# main.net
KiCad netlist of a schematic drawn in EAGLE
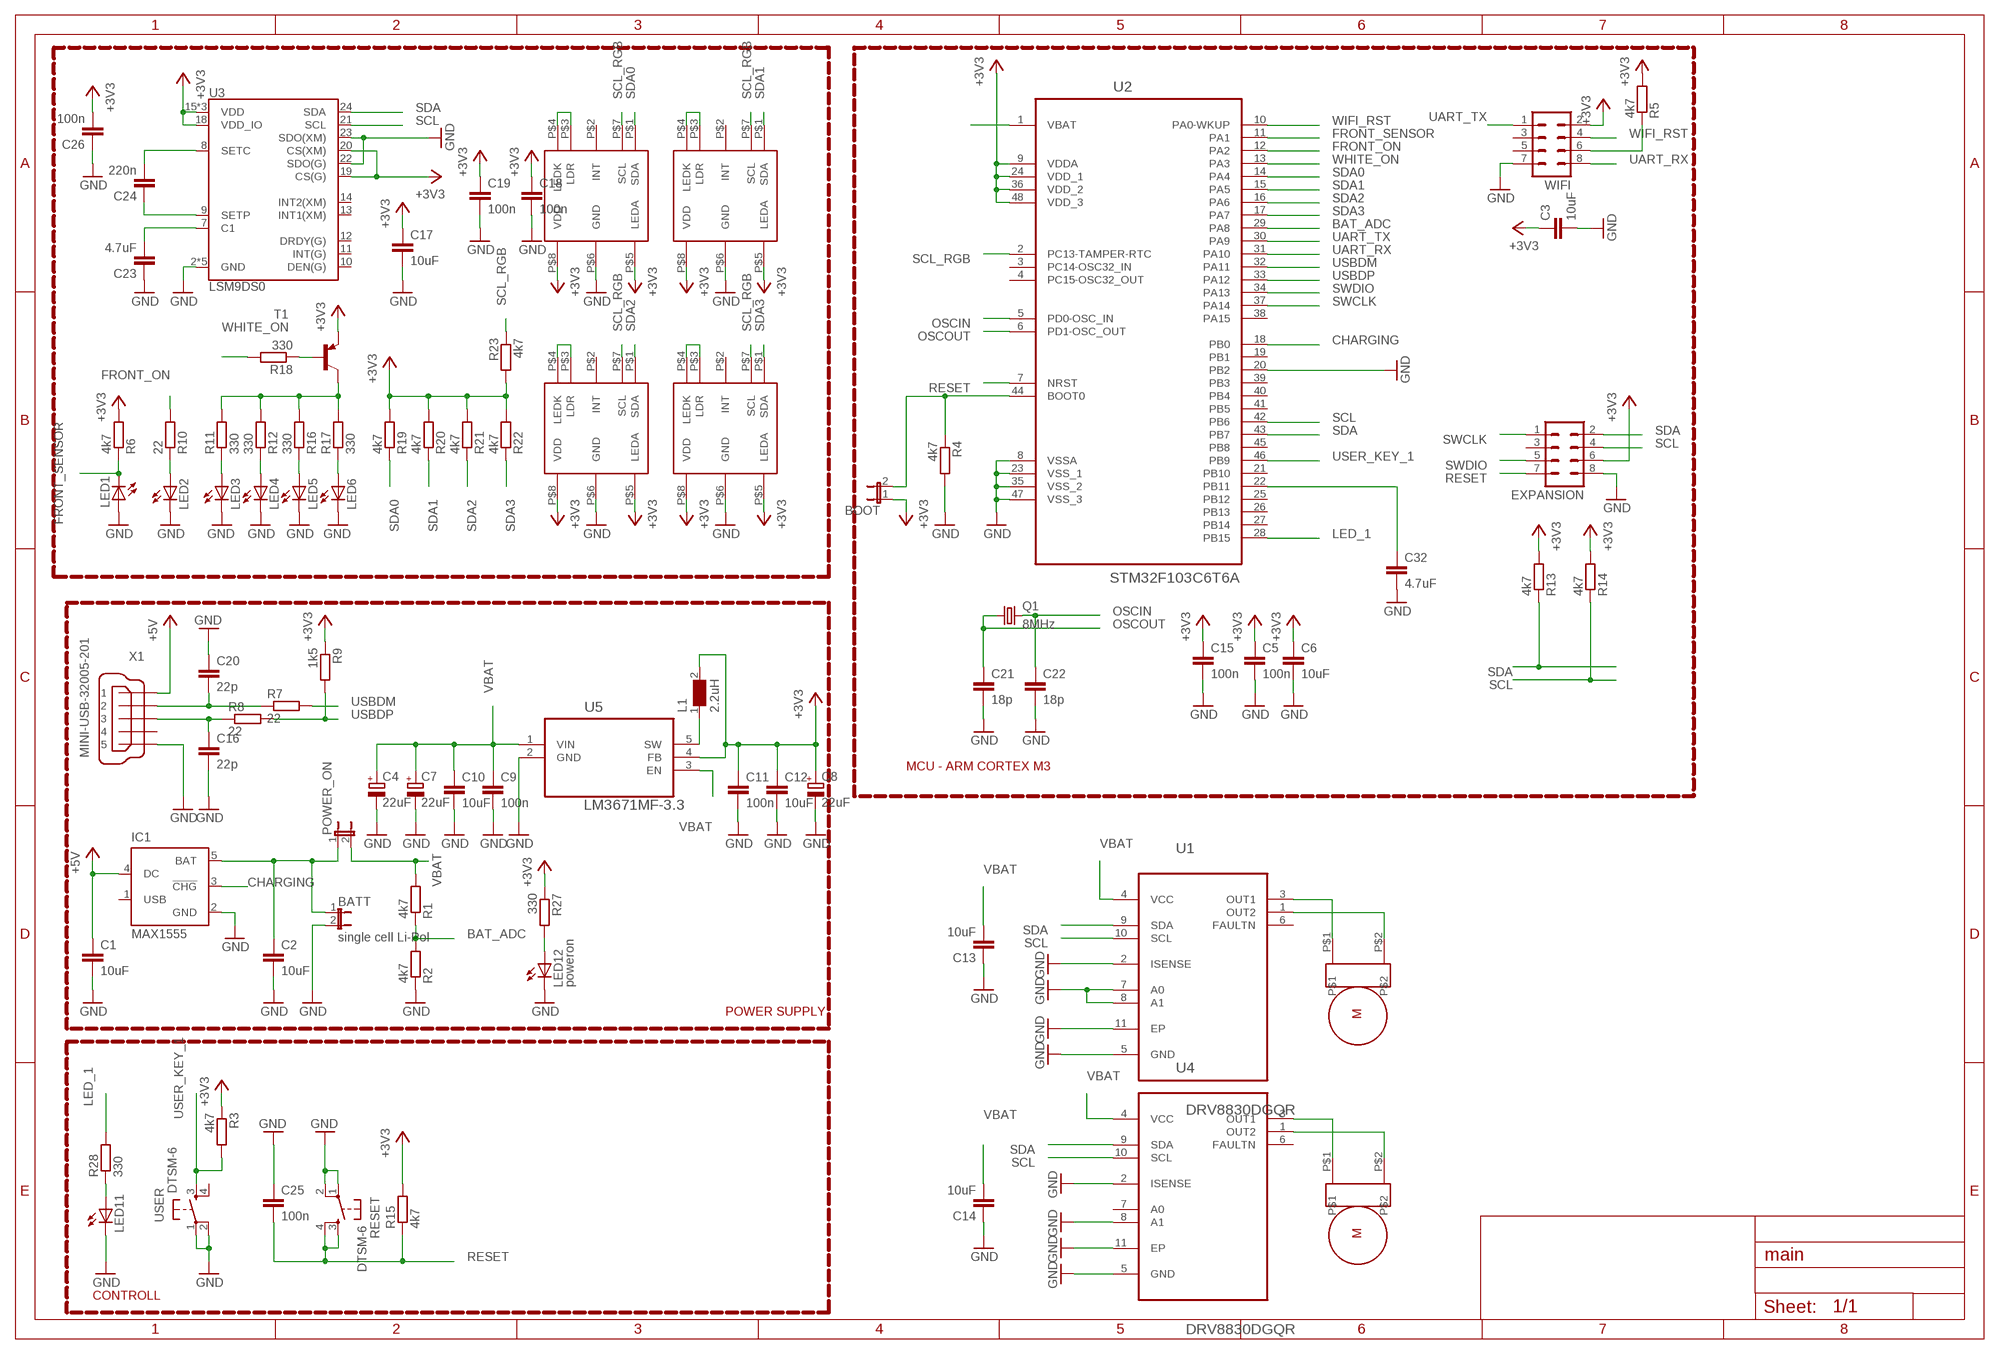
[diagram p0: schematic, sheet 1]

(export (version "E")
  (design (tool "Eeschema 10.0.6"))
  (components
    (comp (ref "BATT")
      (value "single cell Li-Pol")
      (footprint "eagle-import:JP1")
      (libsource (lib "eagle-import") (part "JP1E"))
    )
    (comp (ref "BOOT")
      (value "JP1E")
      (footprint "eagle-import:JP1")
      (libsource (lib "eagle-import") (part "JP1E"))
    )
    (comp (ref "C1")
      (value "10uF")
      (footprint "eagle-import:C0805")
      (libsource (lib "eagle-import") (part "C-EUC0805"))
    )
    (comp (ref "C2")
      (value "10uF")
      (footprint "eagle-import:C0805")
      (libsource (lib "eagle-import") (part "C-EUC0805"))
    )
    (comp (ref "C3")
      (value "10uF")
      (footprint "eagle-import:C0805")
      (libsource (lib "eagle-import") (part "C-EUC0805"))
    )
    (comp (ref "C4")
      (value "22uF")
      (footprint "eagle-import:153CLV-0505")
      (libsource (lib "eagle-import") (part "CPOL-EU153CLV-0505"))
    )
    (comp (ref "C5")
      (value "100n")
      (footprint "eagle-import:C0805")
      (libsource (lib "eagle-import") (part "C-EUC0805"))
    )
    (comp (ref "C6")
      (value "10uF")
      (footprint "eagle-import:C0805")
      (libsource (lib "eagle-import") (part "C-EUC0805"))
    )
    (comp (ref "C7")
      (value "22uF")
      (footprint "eagle-import:153CLV-0505")
      (libsource (lib "eagle-import") (part "CPOL-EU153CLV-0505"))
    )
    (comp (ref "C8")
      (value "22uF")
      (footprint "eagle-import:153CLV-0505")
      (libsource (lib "eagle-import") (part "CPOL-EU153CLV-0505"))
    )
    (comp (ref "C9")
      (value "100n")
      (footprint "eagle-import:C0805")
      (libsource (lib "eagle-import") (part "C-EUC0805"))
    )
    (comp (ref "C10")
      (value "10uF")
      (footprint "eagle-import:C0805")
      (libsource (lib "eagle-import") (part "C-EUC0805"))
    )
    (comp (ref "C11")
      (value "100n")
      (footprint "eagle-import:C0805")
      (libsource (lib "eagle-import") (part "C-EUC0805"))
    )
    (comp (ref "C12")
      (value "10uF")
      (footprint "eagle-import:C0805")
      (libsource (lib "eagle-import") (part "C-EUC0805"))
    )
    (comp (ref "C13")
      (value "10uF")
      (footprint "eagle-import:C0805")
      (libsource (lib "eagle-import") (part "C-EUC0805"))
    )
    (comp (ref "C14")
      (value "10uF")
      (footprint "eagle-import:C0805")
      (libsource (lib "eagle-import") (part "C-EUC0805"))
    )
    (comp (ref "C15")
      (value "100n")
      (footprint "eagle-import:C0805")
      (libsource (lib "eagle-import") (part "C-EUC0805"))
    )
    (comp (ref "C16")
      (value "22p")
      (footprint "eagle-import:C0805")
      (libsource (lib "eagle-import") (part "C-EUC0805"))
    )
    (comp (ref "C17")
      (value "10uF")
      (footprint "eagle-import:C0805")
      (libsource (lib "eagle-import") (part "C-EUC0805"))
    )
    (comp (ref "C18")
      (value "100n")
      (footprint "eagle-import:C0805")
      (libsource (lib "eagle-import") (part "C-EUC0805"))
    )
    (comp (ref "C19")
      (value "100n")
      (footprint "eagle-import:C0805")
      (libsource (lib "eagle-import") (part "C-EUC0805"))
    )
    (comp (ref "C20")
      (value "22p")
      (footprint "eagle-import:C0805")
      (libsource (lib "eagle-import") (part "C-EUC0805"))
    )
    (comp (ref "C21")
      (value "18p")
      (footprint "eagle-import:C0805")
      (libsource (lib "eagle-import") (part "C-EUC0805"))
    )
    (comp (ref "C22")
      (value "18p")
      (footprint "eagle-import:C0805")
      (libsource (lib "eagle-import") (part "C-EUC0805"))
    )
    (comp (ref "C23")
      (value "4.7uF")
      (footprint "eagle-import:C0805")
      (libsource (lib "eagle-import") (part "C-EUC0805"))
    )
    (comp (ref "C24")
      (value "220n")
      (footprint "eagle-import:C0805")
      (libsource (lib "eagle-import") (part "C-EUC0805"))
    )
    (comp (ref "C25")
      (value "100n")
      (footprint "eagle-import:C0805")
      (libsource (lib "eagle-import") (part "C-EUC0805"))
    )
    (comp (ref "C26")
      (value "100n")
      (footprint "eagle-import:C0805")
      (libsource (lib "eagle-import") (part "C-EUC0805"))
    )
    (comp (ref "C32")
      (value "4.7uF")
      (footprint "eagle-import:C0805")
      (libsource (lib "eagle-import") (part "C-EUC0805"))
    )
    (comp (ref "EXPANSION")
      (value "MA04-2")
      (footprint "eagle-import:MA04-2")
      (libsource (lib "eagle-import") (part "MA04-2"))
    )
    (comp (ref "IC1")
      (value "MAX1555")
      (footprint "eagle-import:SOT23-5L")
      (fields (field (name "MF") "MAXIM") (field (name "MPN") "MAX1555EZK+T"))
      (libsource (lib "eagle-import") (part "MAX1555"))
    )
    (comp (ref "L1")
      (value "2.2uH")
      (footprint "eagle-import:WE-LQ_M")
      (fields (field (name "MPN") "744032002 "))
      (libsource (lib "eagle-import") (part "WE-LQ_M-744032002"))
    )
    (comp (ref "LED1")
      (value "LED5MM")
      (footprint "eagle-import:LED5MM")
      (libsource (lib "eagle-import") (part "my_parts_LED5MM"))
    )
    (comp (ref "LED2")
      (value "LED5MM")
      (footprint "eagle-import:LED5MM")
      (libsource (lib "eagle-import") (part "my_parts_LED5MM"))
    )
    (comp (ref "LED3")
      (value "LEDCHIPLED_1206")
      (footprint "eagle-import:CHIPLED_1206")
      (libsource (lib "eagle-import") (part "LEDCHIPLED_1206"))
    )
    (comp (ref "LED4")
      (value "LEDCHIPLED_1206")
      (footprint "eagle-import:CHIPLED_1206")
      (libsource (lib "eagle-import") (part "LEDCHIPLED_1206"))
    )
    (comp (ref "LED5")
      (value "LEDCHIPLED_1206")
      (footprint "eagle-import:CHIPLED_1206")
      (libsource (lib "eagle-import") (part "LEDCHIPLED_1206"))
    )
    (comp (ref "LED6")
      (value "LEDCHIPLED_1206")
      (footprint "eagle-import:CHIPLED_1206")
      (libsource (lib "eagle-import") (part "LEDCHIPLED_1206"))
    )
    (comp (ref "LED11")
      (value "LEDCHIPLED_1206")
      (footprint "eagle-import:CHIPLED_1206")
      (libsource (lib "eagle-import") (part "LEDCHIPLED_1206"))
    )
    (comp (ref "LED12")
      (value "poweron")
      (footprint "eagle-import:CHIPLED_1206")
      (libsource (lib "eagle-import") (part "LEDCHIPLED_1206"))
    )
    (comp (ref "POWER_ON")
      (value "JP1E")
      (footprint "eagle-import:JP1")
      (libsource (lib "eagle-import") (part "JP1E"))
    )
    (comp (ref "Q1")
      (value "8MHz")
      (footprint "eagle-import:CTS406")
      (libsource (lib "eagle-import") (part "CRYSTALCTS406"))
    )
    (comp (ref "R1")
      (value "4k7")
      (footprint "eagle-import:M0805")
      (libsource (lib "eagle-import") (part "R-EU_M0805"))
    )
    (comp (ref "R2")
      (value "4k7")
      (footprint "eagle-import:M0805")
      (libsource (lib "eagle-import") (part "R-EU_M0805"))
    )
    (comp (ref "R3")
      (value "4k7")
      (footprint "eagle-import:M0805")
      (libsource (lib "eagle-import") (part "R-EU_M0805"))
    )
    (comp (ref "R4")
      (value "4k7")
      (footprint "eagle-import:M0805")
      (libsource (lib "eagle-import") (part "R-EU_M0805"))
    )
    (comp (ref "R5")
      (value "4k7")
      (footprint "eagle-import:M0805")
      (libsource (lib "eagle-import") (part "R-EU_M0805"))
    )
    (comp (ref "R6")
      (value "4k7")
      (footprint "eagle-import:M0805")
      (libsource (lib "eagle-import") (part "R-EU_M0805"))
    )
    (comp (ref "R7")
      (value "22")
      (footprint "eagle-import:M0805")
      (libsource (lib "eagle-import") (part "R-EU_M0805"))
    )
    (comp (ref "R8")
      (value "22")
      (footprint "eagle-import:M0805")
      (libsource (lib "eagle-import") (part "R-EU_M0805"))
    )
    (comp (ref "R9")
      (value "1k5")
      (footprint "eagle-import:M0805")
      (libsource (lib "eagle-import") (part "R-EU_M0805"))
    )
    (comp (ref "R10")
      (value "22")
      (footprint "eagle-import:M0805")
      (libsource (lib "eagle-import") (part "R-EU_M0805"))
    )
    (comp (ref "R11")
      (value "330")
      (footprint "eagle-import:M0805")
      (libsource (lib "eagle-import") (part "R-EU_M0805"))
    )
    (comp (ref "R12")
      (value "330")
      (footprint "eagle-import:M0805")
      (libsource (lib "eagle-import") (part "R-EU_M0805"))
    )
    (comp (ref "R13")
      (value "4k7")
      (footprint "eagle-import:M0805")
      (libsource (lib "eagle-import") (part "R-EU_M0805"))
    )
    (comp (ref "R14")
      (value "4k7")
      (footprint "eagle-import:M0805")
      (libsource (lib "eagle-import") (part "R-EU_M0805"))
    )
    (comp (ref "R15")
      (value "4k7")
      (footprint "eagle-import:M0805")
      (libsource (lib "eagle-import") (part "R-EU_M0805"))
    )
    (comp (ref "R16")
      (value "330")
      (footprint "eagle-import:M0805")
      (libsource (lib "eagle-import") (part "R-EU_M0805"))
    )
    (comp (ref "R17")
      (value "330")
      (footprint "eagle-import:M0805")
      (libsource (lib "eagle-import") (part "R-EU_M0805"))
    )
    (comp (ref "R18")
      (value "330")
      (footprint "eagle-import:M0805")
      (libsource (lib "eagle-import") (part "R-EU_M0805"))
    )
    (comp (ref "R19")
      (value "4k7")
      (footprint "eagle-import:M0805")
      (libsource (lib "eagle-import") (part "R-EU_M0805"))
    )
    (comp (ref "R20")
      (value "4k7")
      (footprint "eagle-import:M0805")
      (libsource (lib "eagle-import") (part "R-EU_M0805"))
    )
    (comp (ref "R21")
      (value "4k7")
      (footprint "eagle-import:M0805")
      (libsource (lib "eagle-import") (part "R-EU_M0805"))
    )
    (comp (ref "R22")
      (value "4k7")
      (footprint "eagle-import:M0805")
      (libsource (lib "eagle-import") (part "R-EU_M0805"))
    )
    (comp (ref "R23")
      (value "4k7")
      (footprint "eagle-import:M0805")
      (libsource (lib "eagle-import") (part "R-EU_M0805"))
    )
    (comp (ref "R27")
      (value "330")
      (footprint "eagle-import:M0805")
      (libsource (lib "eagle-import") (part "R-EU_M0805"))
    )
    (comp (ref "R28")
      (value "330")
      (footprint "eagle-import:M0805")
      (libsource (lib "eagle-import") (part "R-EU_M0805"))
    )
    (comp (ref "RESET")
      (value "DTSM-6")
      (footprint "eagle-import:DTSM-6")
      (libsource (lib "eagle-import") (part "DTSM-6"))
    )
    (comp (ref "T1")
      (value "BC857A-PNP-SOT23-BEC")
      (footprint "eagle-import:SOT23-BEC")
      (libsource (lib "eagle-import") (part "-PNP-SOT23-BECBC857A"))
    )
    (comp (ref "U$1")
      (value "APDS9950")
      (footprint "eagle-import:APDS9950")
      (libsource (lib "eagle-import") (part "APDS9950"))
    )
    (comp (ref "U$2")
      (value "APDS9950")
      (footprint "eagle-import:APDS9950")
      (libsource (lib "eagle-import") (part "APDS9950"))
    )
    (comp (ref "U$3")
      (value "APDS9950")
      (footprint "eagle-import:APDS9950")
      (libsource (lib "eagle-import") (part "APDS9950"))
    )
    (comp (ref "U$4")
      (value "APDS9950")
      (footprint "eagle-import:APDS9950")
      (libsource (lib "eagle-import") (part "APDS9950"))
    )
    (comp (ref "U$5")
      (value "MICRO_METAL_GEAR_MOTOR")
      (footprint "eagle-import:MICRO_METAL_GEAR_MOTOR")
      (libsource (lib "eagle-import") (part "MICRO_METAL_GEAR_MOTOR"))
    )
    (comp (ref "U$6")
      (value "MICRO_METAL_GEAR_MOTOR")
      (footprint "eagle-import:MICRO_METAL_GEAR_MOTOR")
      (libsource (lib "eagle-import") (part "MICRO_METAL_GEAR_MOTOR"))
    )
    (comp (ref "U1")
      (value "DRV8830DGQR")
      (footprint "eagle-import:SOP65P640X110-15N")
      (libsource (lib "eagle-import") (part "DRV8830DGQR"))
    )
    (comp (ref "U2")
      (value "STM32F103C6T6A")
      (footprint "eagle-import:QFP50P900X900X160-48N")
      (libsource (lib "eagle-import") (part "STM32F103C6T6A"))
    )
    (comp (ref "U3")
      (value "LSM9DS0")
      (footprint "eagle-import:LGA-24")
      (libsource (lib "eagle-import") (part "LSM9DS0"))
    )
    (comp (ref "U4")
      (value "DRV8830DGQR")
      (footprint "eagle-import:SOP65P640X110-15N")
      (libsource (lib "eagle-import") (part "DRV8830DGQR"))
    )
    (comp (ref "U5")
      (value "LM3671MF-3.3")
      (footprint "eagle-import:SOT95P284X122-5N")
      (libsource (lib "eagle-import") (part "LM3671MF-3.3"))
    )
    (comp (ref "USER")
      (value "DTSM-6")
      (footprint "eagle-import:DTSM-6")
      (libsource (lib "eagle-import") (part "DTSM-6"))
    )
    (comp (ref "WIFI")
      (value "MA04-2")
      (footprint "eagle-import:MA04-2")
      (libsource (lib "eagle-import") (part "MA04-2"))
    )
    (comp (ref "X1")
      (value "MINI-USB-32005-201")
      (footprint "eagle-import:32005-201")
      (libsource (lib "eagle-import") (part "MINI-USB-32005-201"))
    )
  )
  (nets
    (net (code "1") (name "+3V3") (class "Default")
      (node (ref "BOOT") (pin "1") (pinfunction "1_1") (pintype "passive"))
      (node (ref "C11") (pin "1") (pinfunction "1_1") (pintype "passive"))
      (node (ref "C12") (pin "1") (pinfunction "1_1") (pintype "passive"))
      (node (ref "C15") (pin "1") (pinfunction "1_1") (pintype "passive"))
      (node (ref "C17") (pin "1") (pinfunction "1_1") (pintype "passive"))
      (node (ref "C18") (pin "1") (pinfunction "1_1") (pintype "passive"))
      (node (ref "C19") (pin "1") (pinfunction "1_1") (pintype "passive"))
      (node (ref "C26") (pin "2") (pinfunction "2_2") (pintype "passive"))
      (node (ref "C3") (pin "1") (pinfunction "1_1") (pintype "passive"))
      (node (ref "C5") (pin "1") (pinfunction "1_1") (pintype "passive"))
      (node (ref "C6") (pin "1") (pinfunction "1_1") (pintype "passive"))
      (node (ref "C8") (pin "+") (pinfunction "+_+") (pintype "passive"))
      (node (ref "EXPANSION") (pin "6") (pinfunction "6_6") (pintype "passive"))
      (node (ref "L1") (pin "2") (pinfunction "2_2") (pintype "passive"))
      (node (ref "R13") (pin "2") (pinfunction "2_2") (pintype "passive"))
      (node (ref "R14") (pin "2") (pinfunction "2_2") (pintype "passive"))
      (node (ref "R15") (pin "2") (pinfunction "2_2") (pintype "passive"))
      (node (ref "R19") (pin "2") (pinfunction "2_2") (pintype "passive"))
      (node (ref "R20") (pin "2") (pinfunction "2_2") (pintype "passive"))
      (node (ref "R21") (pin "2") (pinfunction "2_2") (pintype "passive"))
      (node (ref "R22") (pin "2") (pinfunction "2_2") (pintype "passive"))
      (node (ref "R23") (pin "2") (pinfunction "2_2") (pintype "passive"))
      (node (ref "R27") (pin "1") (pinfunction "1_1") (pintype "passive"))
      (node (ref "R3") (pin "1") (pinfunction "1_1") (pintype "passive"))
      (node (ref "R5") (pin "2") (pinfunction "2_2") (pintype "passive"))
      (node (ref "R6") (pin "2") (pinfunction "2_2") (pintype "passive"))
      (node (ref "R9") (pin "1") (pinfunction "1_1") (pintype "passive"))
      (node (ref "T1") (pin "E") (pinfunction "E_E") (pintype "passive"))
      (node (ref "U$1") (pin "P$5") (pinfunction "LEDA_P$5") (pintype "bidirectional"))
      (node (ref "U$1") (pin "P$8") (pinfunction "VDD_P$8") (pintype "bidirectional"))
      (node (ref "U$2") (pin "P$5") (pinfunction "LEDA_P$5") (pintype "bidirectional"))
      (node (ref "U$2") (pin "P$8") (pinfunction "VDD_P$8") (pintype "bidirectional"))
      (node (ref "U$3") (pin "P$5") (pinfunction "LEDA_P$5") (pintype "bidirectional"))
      (node (ref "U$3") (pin "P$8") (pinfunction "VDD_P$8") (pintype "bidirectional"))
      (node (ref "U$4") (pin "P$5") (pinfunction "LEDA_P$5") (pintype "bidirectional"))
      (node (ref "U$4") (pin "P$8") (pinfunction "VDD_P$8") (pintype "bidirectional"))
      (node (ref "U2") (pin "24") (pinfunction "VDD_1_24") (pintype "power_in"))
      (node (ref "U2") (pin "36") (pinfunction "VDD_2_36") (pintype "power_in"))
      (node (ref "U2") (pin "48") (pinfunction "VDD_3_48") (pintype "power_in"))
      (node (ref "U2") (pin "9") (pinfunction "VDDA_9") (pintype "power_in"))
      (node (ref "U3") (pin "15") (pinfunction "VDD_15") (pintype "bidirectional"))
      (node (ref "U3") (pin "16") (pinfunction "VDD_16") (pintype "bidirectional"))
      (node (ref "U3") (pin "17") (pinfunction "VDD_17") (pintype "bidirectional"))
      (node (ref "U3") (pin "18") (pinfunction "VDD_IO_18") (pintype "bidirectional"))
      (node (ref "U3") (pin "19") (pinfunction "CS(G)_19") (pintype "bidirectional"))
      (node (ref "U3") (pin "20") (pinfunction "CS(XM)_20") (pintype "bidirectional"))
      (node (ref "U5") (pin "4") (pinfunction "FB_4") (pintype "passive"))
      (node (ref "WIFI") (pin "2") (pinfunction "2_2") (pintype "passive"))
    )
    (net (code "2") (name "+5V") (class "Default")
      (node (ref "C1") (pin "1") (pinfunction "1_1") (pintype "passive"))
      (node (ref "IC1") (pin "4") (pinfunction "DC_4") (pintype "input"))
      (node (ref "X1") (pin "1") (pinfunction "1_1") (pintype "passive"))
    )
    (net (code "3") (name "/BAT_ADC") (class "Default")
      (node (ref "R1") (pin "1") (pinfunction "1_1") (pintype "passive"))
      (node (ref "R2") (pin "2") (pinfunction "2_2") (pintype "passive"))
      (node (ref "U2") (pin "29") (pinfunction "PA8_29") (pintype "bidirectional"))
    )
    (net (code "4") (name "/CHARGING") (class "Default")
      (node (ref "IC1") (pin "3") (pinfunction "~{CHG}_3") (pintype "output"))
      (node (ref "U2") (pin "18") (pinfunction "PB0_18") (pintype "bidirectional"))
    )
    (net (code "5") (name "/FRONT_ON") (class "Default")
      (node (ref "R10") (pin "2") (pinfunction "2_2") (pintype "passive"))
      (node (ref "U2") (pin "12") (pinfunction "PA2_12") (pintype "bidirectional"))
    )
    (net (code "6") (name "/FRONT_SENSOR") (class "Default")
      (node (ref "LED1") (pin "K") (pinfunction "C_K") (pintype "passive"))
      (node (ref "R6") (pin "1") (pinfunction "1_1") (pintype "passive"))
      (node (ref "U2") (pin "11") (pinfunction "PA1_11") (pintype "bidirectional"))
    )
    (net (code "7") (name "/LED_1") (class "Default")
      (node (ref "R28") (pin "2") (pinfunction "2_2") (pintype "passive"))
      (node (ref "U2") (pin "28") (pinfunction "PB15_28") (pintype "bidirectional"))
    )
    (net (code "8") (name "/OSCIN") (class "Default")
      (node (ref "C22") (pin "1") (pinfunction "1_1") (pintype "passive"))
      (node (ref "Q1") (pin "3") (pinfunction "2_3") (pintype "passive"))
      (node (ref "U2") (pin "5") (pinfunction "PD0-OSC_IN_5") (pintype "bidirectional"))
    )
    (net (code "9") (name "/OSCOUT") (class "Default")
      (node (ref "C21") (pin "1") (pinfunction "1_1") (pintype "passive"))
      (node (ref "Q1") (pin "1") (pinfunction "1_1") (pintype "passive"))
      (node (ref "U2") (pin "6") (pinfunction "PD1-OSC_OUT_6") (pintype "bidirectional"))
    )
    (net (code "10") (name "/RESET") (class "Default")
      (node (ref "C25") (pin "2") (pinfunction "2_2") (pintype "passive"))
      (node (ref "EXPANSION") (pin "7") (pinfunction "7_7") (pintype "passive"))
      (node (ref "R15") (pin "1") (pinfunction "1_1") (pintype "passive"))
      (node (ref "RESET") (pin "3") (pinfunction "3_3") (pintype "passive"))
      (node (ref "RESET") (pin "4") (pinfunction "4_4") (pintype "passive"))
      (node (ref "U2") (pin "7") (pinfunction "NRST_7") (pintype "bidirectional"))
    )
    (net (code "11") (name "/SCL") (class "Default")
      (node (ref "EXPANSION") (pin "4") (pinfunction "4_4") (pintype "passive"))
      (node (ref "R14") (pin "1") (pinfunction "1_1") (pintype "passive"))
      (node (ref "U1") (pin "10") (pinfunction "SCL_10") (pintype "input"))
      (node (ref "U2") (pin "42") (pinfunction "PB6_42") (pintype "bidirectional"))
      (node (ref "U3") (pin "21") (pinfunction "SCL_21") (pintype "bidirectional"))
      (node (ref "U4") (pin "10") (pinfunction "SCL_10") (pintype "input"))
    )
    (net (code "12") (name "/SCL_RGB") (class "Default")
      (node (ref "R23") (pin "1") (pinfunction "1_1") (pintype "passive"))
      (node (ref "U$1") (pin "P$7") (pinfunction "SCL_P$7") (pintype "bidirectional"))
      (node (ref "U$2") (pin "P$7") (pinfunction "SCL_P$7") (pintype "bidirectional"))
      (node (ref "U$3") (pin "P$7") (pinfunction "SCL_P$7") (pintype "bidirectional"))
      (node (ref "U$4") (pin "P$7") (pinfunction "SCL_P$7") (pintype "bidirectional"))
      (node (ref "U2") (pin "2") (pinfunction "PC13-TAMPER-RTC_2") (pintype "bidirectional"))
    )
    (net (code "13") (name "/SDA") (class "Default")
      (node (ref "EXPANSION") (pin "2") (pinfunction "2_2") (pintype "passive"))
      (node (ref "R13") (pin "1") (pinfunction "1_1") (pintype "passive"))
      (node (ref "U1") (pin "9") (pinfunction "SDA_9") (pintype "bidirectional"))
      (node (ref "U2") (pin "43") (pinfunction "PB7_43") (pintype "bidirectional"))
      (node (ref "U3") (pin "24") (pinfunction "SDA_24") (pintype "bidirectional"))
      (node (ref "U4") (pin "9") (pinfunction "SDA_9") (pintype "bidirectional"))
    )
    (net (code "14") (name "/SDA0") (class "Default")
      (node (ref "R19") (pin "1") (pinfunction "1_1") (pintype "passive"))
      (node (ref "U$1") (pin "P$1") (pinfunction "SDA_P$1") (pintype "bidirectional"))
      (node (ref "U2") (pin "14") (pinfunction "PA4_14") (pintype "bidirectional"))
    )
    (net (code "15") (name "/SDA1") (class "Default")
      (node (ref "R20") (pin "1") (pinfunction "1_1") (pintype "passive"))
      (node (ref "U$2") (pin "P$1") (pinfunction "SDA_P$1") (pintype "bidirectional"))
      (node (ref "U2") (pin "15") (pinfunction "PA5_15") (pintype "bidirectional"))
    )
    (net (code "16") (name "/SDA2") (class "Default")
      (node (ref "R21") (pin "1") (pinfunction "1_1") (pintype "passive"))
      (node (ref "U$3") (pin "P$1") (pinfunction "SDA_P$1") (pintype "bidirectional"))
      (node (ref "U2") (pin "16") (pinfunction "PA6_16") (pintype "bidirectional"))
    )
    (net (code "17") (name "/SDA3") (class "Default")
      (node (ref "R22") (pin "1") (pinfunction "1_1") (pintype "passive"))
      (node (ref "U$4") (pin "P$1") (pinfunction "SDA_P$1") (pintype "bidirectional"))
      (node (ref "U2") (pin "17") (pinfunction "PA7_17") (pintype "bidirectional"))
    )
    (net (code "18") (name "/SWCLK") (class "Default")
      (node (ref "EXPANSION") (pin "1") (pinfunction "1_1") (pintype "passive"))
      (node (ref "U2") (pin "37") (pinfunction "PA14_37") (pintype "bidirectional"))
    )
    (net (code "19") (name "/SWDIO") (class "Default")
      (node (ref "EXPANSION") (pin "5") (pinfunction "5_5") (pintype "passive"))
      (node (ref "U2") (pin "34") (pinfunction "PA13_34") (pintype "bidirectional"))
    )
    (net (code "20") (name "/UART_RX") (class "Default")
      (node (ref "U2") (pin "31") (pinfunction "PA10_31") (pintype "bidirectional"))
      (node (ref "WIFI") (pin "8") (pinfunction "8_8") (pintype "passive"))
    )
    (net (code "21") (name "/UART_TX") (class "Default")
      (node (ref "U2") (pin "30") (pinfunction "PA9_30") (pintype "bidirectional"))
      (node (ref "WIFI") (pin "1") (pinfunction "1_1") (pintype "passive"))
    )
    (net (code "22") (name "/USBDM") (class "Default")
      (node (ref "R7") (pin "2") (pinfunction "2_2") (pintype "passive"))
      (node (ref "U2") (pin "32") (pinfunction "PA11_32") (pintype "bidirectional"))
    )
    (net (code "23") (name "/USBDP") (class "Default")
      (node (ref "R8") (pin "2") (pinfunction "2_2") (pintype "passive"))
      (node (ref "R9") (pin "2") (pinfunction "2_2") (pintype "passive"))
      (node (ref "U2") (pin "33") (pinfunction "PA12_33") (pintype "bidirectional"))
    )
    (net (code "24") (name "/USER_KEY_1") (class "Default")
      (node (ref "R3") (pin "2") (pinfunction "2_2") (pintype "passive"))
      (node (ref "U2") (pin "46") (pinfunction "PB9_46") (pintype "bidirectional"))
      (node (ref "USER") (pin "3") (pinfunction "3_3") (pintype "passive"))
    )
    (net (code "25") (name "/VBAT") (class "Default")
      (node (ref "C10") (pin "1") (pinfunction "1_1") (pintype "passive"))
      (node (ref "C13") (pin "2") (pinfunction "2_2") (pintype "passive"))
      (node (ref "C14") (pin "2") (pinfunction "2_2") (pintype "passive"))
      (node (ref "C4") (pin "+") (pinfunction "+_+") (pintype "passive"))
      (node (ref "C7") (pin "+") (pinfunction "+_+") (pintype "passive"))
      (node (ref "C9") (pin "1") (pinfunction "1_1") (pintype "passive"))
      (node (ref "POWER_ON") (pin "2") (pinfunction "2_2") (pintype "passive"))
      (node (ref "R1") (pin "2") (pinfunction "2_2") (pintype "passive"))
      (node (ref "U1") (pin "4") (pinfunction "VCC_4") (pintype "power_in"))
      (node (ref "U4") (pin "4") (pinfunction "VCC_4") (pintype "power_in"))
      (node (ref "U5") (pin "1") (pinfunction "VIN_1") (pintype "input"))
      (node (ref "U5") (pin "3") (pinfunction "EN_3") (pintype "passive"))
    )
    (net (code "26") (name "/WHITE_ON") (class "Default")
      (node (ref "R18") (pin "2") (pinfunction "2_2") (pintype "passive"))
      (node (ref "U2") (pin "13") (pinfunction "PA3_13") (pintype "bidirectional"))
    )
    (net (code "27") (name "/WIFI_RST") (class "Default")
      (node (ref "U2") (pin "10") (pinfunction "PA0-WKUP_10") (pintype "bidirectional"))
      (node (ref "WIFI") (pin "4") (pinfunction "4_4") (pintype "passive"))
    )
    (net (code "28") (name "GND") (class "Default")
      (node (ref "BATT") (pin "2") (pinfunction "2_2") (pintype "passive"))
      (node (ref "C1") (pin "2") (pinfunction "2_2") (pintype "passive"))
      (node (ref "C10") (pin "2") (pinfunction "2_2") (pintype "passive"))
      (node (ref "C11") (pin "2") (pinfunction "2_2") (pintype "passive"))
      (node (ref "C12") (pin "2") (pinfunction "2_2") (pintype "passive"))
      (node (ref "C13") (pin "1") (pinfunction "1_1") (pintype "passive"))
      (node (ref "C14") (pin "1") (pinfunction "1_1") (pintype "passive"))
      (node (ref "C15") (pin "2") (pinfunction "2_2") (pintype "passive"))
      (node (ref "C16") (pin "2") (pinfunction "2_2") (pintype "passive"))
      (node (ref "C17") (pin "2") (pinfunction "2_2") (pintype "passive"))
      (node (ref "C18") (pin "2") (pinfunction "2_2") (pintype "passive"))
      (node (ref "C19") (pin "2") (pinfunction "2_2") (pintype "passive"))
      (node (ref "C2") (pin "2") (pinfunction "2_2") (pintype "passive"))
      (node (ref "C20") (pin "1") (pinfunction "1_1") (pintype "passive"))
      (node (ref "C21") (pin "2") (pinfunction "2_2") (pintype "passive"))
      (node (ref "C22") (pin "2") (pinfunction "2_2") (pintype "passive"))
      (node (ref "C23") (pin "1") (pinfunction "1_1") (pintype "passive"))
      (node (ref "C25") (pin "1") (pinfunction "1_1") (pintype "passive"))
      (node (ref "C26") (pin "1") (pinfunction "1_1") (pintype "passive"))
      (node (ref "C3") (pin "2") (pinfunction "2_2") (pintype "passive"))
      (node (ref "C32") (pin "2") (pinfunction "2_2") (pintype "passive"))
      (node (ref "C4") (pin "-") (pinfunction "-_-") (pintype "passive"))
      (node (ref "C5") (pin "2") (pinfunction "2_2") (pintype "passive"))
      (node (ref "C6") (pin "2") (pinfunction "2_2") (pintype "passive"))
      (node (ref "C7") (pin "-") (pinfunction "-_-") (pintype "passive"))
      (node (ref "C8") (pin "-") (pinfunction "-_-") (pintype "passive"))
      (node (ref "C9") (pin "2") (pinfunction "2_2") (pintype "passive"))
      (node (ref "EXPANSION") (pin "8") (pinfunction "8_8") (pintype "passive"))
      (node (ref "IC1") (pin "2") (pinfunction "GND_2") (pintype "power_in"))
      (node (ref "LED1") (pin "A") (pinfunction "A_A") (pintype "passive"))
      (node (ref "LED11") (pin "C") (pinfunction "C_C") (pintype "passive"))
      (node (ref "LED12") (pin "C") (pinfunction "C_C") (pintype "passive"))
      (node (ref "LED2") (pin "K") (pinfunction "C_K") (pintype "passive"))
      (node (ref "LED3") (pin "C") (pinfunction "C_C") (pintype "passive"))
      (node (ref "LED4") (pin "C") (pinfunction "C_C") (pintype "passive"))
      (node (ref "LED5") (pin "C") (pinfunction "C_C") (pintype "passive"))
      (node (ref "LED6") (pin "C") (pinfunction "C_C") (pintype "passive"))
      (node (ref "R2") (pin "1") (pinfunction "1_1") (pintype "passive"))
      (node (ref "R4") (pin "2") (pinfunction "2_2") (pintype "passive"))
      (node (ref "RESET") (pin "1") (pinfunction "1_1") (pintype "passive"))
      (node (ref "RESET") (pin "2") (pinfunction "2_2") (pintype "passive"))
      (node (ref "U$1") (pin "P$6") (pinfunction "GND_P$6") (pintype "bidirectional"))
      (node (ref "U$2") (pin "P$6") (pinfunction "GND_P$6") (pintype "bidirectional"))
      (node (ref "U$3") (pin "P$6") (pinfunction "GND_P$6") (pintype "bidirectional"))
      (node (ref "U$4") (pin "P$6") (pinfunction "GND_P$6") (pintype "bidirectional"))
      (node (ref "U1") (pin "11") (pinfunction "EP_11") (pintype "passive"))
      (node (ref "U1") (pin "2") (pinfunction "ISENSE_2") (pintype "input"))
      (node (ref "U1") (pin "5") (pinfunction "GND_5") (pintype "passive"))
      (node (ref "U1") (pin "7") (pinfunction "A0_7") (pintype "input"))
      (node (ref "U1") (pin "8") (pinfunction "A1_8") (pintype "input"))
      (node (ref "U2") (pin "20") (pinfunction "PB2_20") (pintype "bidirectional"))
      (node (ref "U2") (pin "23") (pinfunction "VSS_1_23") (pintype "passive"))
      (node (ref "U2") (pin "35") (pinfunction "VSS_2_35") (pintype "passive"))
      (node (ref "U2") (pin "47") (pinfunction "VSS_3_47") (pintype "passive"))
      (node (ref "U2") (pin "8") (pinfunction "VSSA_8") (pintype "passive"))
      (node (ref "U3") (pin "2") (pinfunction "GND_2") (pintype "bidirectional"))
      (node (ref "U3") (pin "22") (pinfunction "SDO(G)_22") (pintype "bidirectional"))
      (node (ref "U3") (pin "23") (pinfunction "SDO(XM)_23") (pintype "bidirectional"))
      (node (ref "U3") (pin "3") (pinfunction "GND_3") (pintype "bidirectional"))
      (node (ref "U3") (pin "4") (pinfunction "GND_4") (pintype "bidirectional"))
      (node (ref "U3") (pin "5") (pinfunction "GND_5") (pintype "bidirectional"))
      (node (ref "U3") (pin "6") (pinfunction "GND_6") (pintype "bidirectional"))
      (node (ref "U4") (pin "11") (pinfunction "EP_11") (pintype "passive"))
      (node (ref "U4") (pin "2") (pinfunction "ISENSE_2") (pintype "input"))
      (node (ref "U4") (pin "5") (pinfunction "GND_5") (pintype "passive"))
      (node (ref "U4") (pin "8") (pinfunction "A1_8") (pintype "input"))
      (node (ref "U5") (pin "2") (pinfunction "GND_2") (pintype "passive"))
      (node (ref "USER") (pin "1") (pinfunction "1_1") (pintype "passive"))
      (node (ref "USER") (pin "2") (pinfunction "2_2") (pintype "passive"))
      (node (ref "WIFI") (pin "7") (pinfunction "7_7") (pintype "passive"))
      (node (ref "X1") (pin "5") (pinfunction "5_5") (pintype "passive"))
    )
    (net (code "29") (name "Net-(C16-Pad1)") (class "Default")
      (node (ref "C16") (pin "1") (pinfunction "1_1") (pintype "passive"))
      (node (ref "R8") (pin "1") (pinfunction "1_1") (pintype "passive"))
      (node (ref "X1") (pin "3") (pinfunction "3_3") (pintype "passive"))
    )
    (net (code "30") (name "Net-(C20-Pad2)") (class "Default")
      (node (ref "C20") (pin "2") (pinfunction "2_2") (pintype "passive"))
      (node (ref "R7") (pin "1") (pinfunction "1_1") (pintype "passive"))
      (node (ref "X1") (pin "2") (pinfunction "2_2") (pintype "passive"))
    )
    (net (code "31") (name "Net-(IC1-BAT)") (class "Default")
      (node (ref "BATT") (pin "1") (pinfunction "1_1") (pintype "passive"))
      (node (ref "C2") (pin "1") (pinfunction "1_1") (pintype "passive"))
      (node (ref "IC1") (pin "5") (pinfunction "BAT_5") (pintype "passive"))
      (node (ref "POWER_ON") (pin "1") (pinfunction "1_1") (pintype "passive"))
    )
    (net (code "32") (name "Net-(LED2-PadA)") (class "Default")
      (node (ref "LED2") (pin "A") (pinfunction "A_A") (pintype "passive"))
      (node (ref "R10") (pin "1") (pinfunction "1_1") (pintype "passive"))
    )
    (net (code "33") (name "Net-(LED3-PadA)") (class "Default")
      (node (ref "LED3") (pin "A") (pinfunction "A_A") (pintype "passive"))
      (node (ref "R11") (pin "1") (pinfunction "1_1") (pintype "passive"))
    )
    (net (code "34") (name "Net-(LED4-PadA)") (class "Default")
      (node (ref "LED4") (pin "A") (pinfunction "A_A") (pintype "passive"))
      (node (ref "R12") (pin "1") (pinfunction "1_1") (pintype "passive"))
    )
    (net (code "35") (name "Net-(LED5-PadA)") (class "Default")
      (node (ref "LED5") (pin "A") (pinfunction "A_A") (pintype "passive"))
      (node (ref "R16") (pin "1") (pinfunction "1_1") (pintype "passive"))
    )
    (net (code "36") (name "Net-(LED6-PadA)") (class "Default")
      (node (ref "LED6") (pin "A") (pinfunction "A_A") (pintype "passive"))
      (node (ref "R17") (pin "1") (pinfunction "1_1") (pintype "passive"))
    )
    (net (code "37") (name "Net-(LED11-PadA)") (class "Default")
      (node (ref "LED11") (pin "A") (pinfunction "A_A") (pintype "passive"))
      (node (ref "R28") (pin "1") (pinfunction "1_1") (pintype "passive"))
    )
    (net (code "38") (name "Net-(LED12-PadA)") (class "Default")
      (node (ref "LED12") (pin "A") (pinfunction "A_A") (pintype "passive"))
      (node (ref "R27") (pin "2") (pinfunction "2_2") (pintype "passive"))
    )
    (net (code "39") (name "Net-(R5-Pad1)") (class "Default")
      (node (ref "R5") (pin "1") (pinfunction "1_1") (pintype "passive"))
      (node (ref "WIFI") (pin "6") (pinfunction "6_6") (pintype "passive"))
    )
    (net (code "40") (name "Net-(R11-Pad2)") (class "Default")
      (node (ref "R11") (pin "2") (pinfunction "2_2") (pintype "passive"))
      (node (ref "R12") (pin "2") (pinfunction "2_2") (pintype "passive"))
      (node (ref "R16") (pin "2") (pinfunction "2_2") (pintype "passive"))
      (node (ref "R17") (pin "2") (pinfunction "2_2") (pintype "passive"))
      (node (ref "T1") (pin "C") (pinfunction "C_C") (pintype "passive"))
    )
    (net (code "41") (name "Net-(R18-Pad1)") (class "Default")
      (node (ref "R18") (pin "1") (pinfunction "1_1") (pintype "passive"))
      (node (ref "T1") (pin "B") (pinfunction "B_B") (pintype "passive"))
    )
    (net (code "42") (name "Net-(U$1-LDR)") (class "Default")
      (node (ref "U$1") (pin "P$3") (pinfunction "LDR_P$3") (pintype "bidirectional"))
      (node (ref "U$1") (pin "P$4") (pinfunction "LEDK_P$4") (pintype "bidirectional"))
    )
    (net (code "43") (name "Net-(U$2-LDR)") (class "Default")
      (node (ref "U$2") (pin "P$3") (pinfunction "LDR_P$3") (pintype "bidirectional"))
      (node (ref "U$2") (pin "P$4") (pinfunction "LEDK_P$4") (pintype "bidirectional"))
    )
    (net (code "44") (name "Net-(U$3-LDR)") (class "Default")
      (node (ref "U$3") (pin "P$3") (pinfunction "LDR_P$3") (pintype "bidirectional"))
      (node (ref "U$3") (pin "P$4") (pinfunction "LEDK_P$4") (pintype "bidirectional"))
    )
    (net (code "45") (name "Net-(U$4-LDR)") (class "Default")
      (node (ref "U$4") (pin "P$3") (pinfunction "LDR_P$3") (pintype "bidirectional"))
      (node (ref "U$4") (pin "P$4") (pinfunction "LEDK_P$4") (pintype "bidirectional"))
    )
    (net (code "46") (name "Net-(U1-OUT1)") (class "Default")
      (node (ref "U$5") (pin "P$1") (pinfunction "P$1_P$1") (pintype "bidirectional"))
      (node (ref "U1") (pin "3") (pinfunction "OUT1_3") (pintype "output"))
    )
    (net (code "47") (name "Net-(U1-OUT2)") (class "Default")
      (node (ref "U$5") (pin "P$2") (pinfunction "P$2_P$2") (pintype "bidirectional"))
      (node (ref "U1") (pin "1") (pinfunction "OUT2_1") (pintype "output"))
    )
    (net (code "48") (name "Net-(U2-BOOT0)") (class "Default")
      (node (ref "BOOT") (pin "2") (pinfunction "2_2") (pintype "passive"))
      (node (ref "R4") (pin "1") (pinfunction "1_1") (pintype "passive"))
      (node (ref "U2") (pin "44") (pinfunction "BOOT0_44") (pintype "input"))
    )
    (net (code "49") (name "Net-(U2-PB11)") (class "Default")
      (node (ref "C32") (pin "1") (pinfunction "1_1") (pintype "passive"))
      (node (ref "U2") (pin "22") (pinfunction "PB11_22") (pintype "bidirectional"))
    )
    (net (code "50") (name "Net-(U3-C1)") (class "Default")
      (node (ref "C23") (pin "2") (pinfunction "2_2") (pintype "passive"))
      (node (ref "U3") (pin "7") (pinfunction "C1_7") (pintype "bidirectional"))
    )
    (net (code "51") (name "Net-(U3-SETC)") (class "Default")
      (node (ref "C24") (pin "2") (pinfunction "2_2") (pintype "passive"))
      (node (ref "U3") (pin "8") (pinfunction "SETC_8") (pintype "bidirectional"))
    )
    (net (code "52") (name "Net-(U3-SETP)") (class "Default")
      (node (ref "C24") (pin "1") (pinfunction "1_1") (pintype "passive"))
      (node (ref "U3") (pin "9") (pinfunction "SETP_9") (pintype "bidirectional"))
    )
    (net (code "53") (name "Net-(U4-OUT1)") (class "Default")
      (node (ref "U$6") (pin "P$1") (pinfunction "P$1_P$1") (pintype "bidirectional"))
      (node (ref "U4") (pin "3") (pinfunction "OUT1_3") (pintype "output"))
    )
    (net (code "54") (name "Net-(U4-OUT2)") (class "Default")
      (node (ref "U$6") (pin "P$2") (pinfunction "P$2_P$2") (pintype "bidirectional"))
      (node (ref "U4") (pin "1") (pinfunction "OUT2_1") (pintype "output"))
    )
    (net (code "55") (name "Net-(U5-SW)") (class "Default")
      (node (ref "L1") (pin "1") (pinfunction "1_1") (pintype "passive"))
      (node (ref "U5") (pin "5") (pinfunction "SW_5") (pintype "output"))
    )
    (net (code "56") (name "unconnected-(EXPANSION-Pad3)") (class "Default")
      (node (ref "EXPANSION") (pin "3") (pinfunction "3_3") (pintype "passive"))
    )
    (net (code "57") (name "unconnected-(IC1-USB-Pad1)") (class "Default")
      (node (ref "IC1") (pin "1") (pinfunction "USB_1") (pintype "input"))
    )
    (net (code "58") (name "unconnected-(U$1-INT-PadP$2)") (class "Default")
      (node (ref "U$1") (pin "P$2") (pinfunction "INT_P$2") (pintype "bidirectional"))
    )
    (net (code "59") (name "unconnected-(U$2-INT-PadP$2)") (class "Default")
      (node (ref "U$2") (pin "P$2") (pinfunction "INT_P$2") (pintype "bidirectional"))
    )
    (net (code "60") (name "unconnected-(U$3-INT-PadP$2)") (class "Default")
      (node (ref "U$3") (pin "P$2") (pinfunction "INT_P$2") (pintype "bidirectional"))
    )
    (net (code "61") (name "unconnected-(U$4-INT-PadP$2)") (class "Default")
      (node (ref "U$4") (pin "P$2") (pinfunction "INT_P$2") (pintype "bidirectional"))
    )
    (net (code "62") (name "unconnected-(U1-FAULTN-Pad6)") (class "Default")
      (node (ref "U1") (pin "6") (pinfunction "FAULTN_6") (pintype "output"))
    )
    (net (code "63") (name "unconnected-(U2-PA15-Pad38)") (class "Default")
      (node (ref "U2") (pin "38") (pinfunction "PA15_38") (pintype "bidirectional"))
    )
    (net (code "64") (name "unconnected-(U2-PB1-Pad19)") (class "Default")
      (node (ref "U2") (pin "19") (pinfunction "PB1_19") (pintype "bidirectional"))
    )
    (net (code "65") (name "unconnected-(U2-PB3-Pad39)") (class "Default")
      (node (ref "U2") (pin "39") (pinfunction "PB3_39") (pintype "bidirectional"))
    )
    (net (code "66") (name "unconnected-(U2-PB4-Pad40)") (class "Default")
      (node (ref "U2") (pin "40") (pinfunction "PB4_40") (pintype "bidirectional"))
    )
    (net (code "67") (name "unconnected-(U2-PB5-Pad41)") (class "Default")
      (node (ref "U2") (pin "41") (pinfunction "PB5_41") (pintype "bidirectional"))
    )
    (net (code "68") (name "unconnected-(U2-PB8-Pad45)") (class "Default")
      (node (ref "U2") (pin "45") (pinfunction "PB8_45") (pintype "bidirectional"))
    )
    (net (code "69") (name "unconnected-(U2-PB10-Pad21)") (class "Default")
      (node (ref "U2") (pin "21") (pinfunction "PB10_21") (pintype "bidirectional"))
    )
    (net (code "70") (name "unconnected-(U2-PB12-Pad25)") (class "Default")
      (node (ref "U2") (pin "25") (pinfunction "PB12_25") (pintype "bidirectional"))
    )
    (net (code "71") (name "unconnected-(U2-PB13-Pad26)") (class "Default")
      (node (ref "U2") (pin "26") (pinfunction "PB13_26") (pintype "bidirectional"))
    )
    (net (code "72") (name "unconnected-(U2-PB14-Pad27)") (class "Default")
      (node (ref "U2") (pin "27") (pinfunction "PB14_27") (pintype "bidirectional"))
    )
    (net (code "73") (name "unconnected-(U2-PC14-OSC32_IN-Pad3)") (class "Default")
      (node (ref "U2") (pin "3") (pinfunction "PC14-OSC32_IN_3") (pintype "bidirectional"))
    )
    (net (code "74") (name "unconnected-(U2-PC15-OSC32_OUT-Pad4)") (class "Default")
      (node (ref "U2") (pin "4") (pinfunction "PC15-OSC32_OUT_4") (pintype "bidirectional"))
    )
    (net (code "75") (name "unconnected-(U2-VBAT-Pad1)") (class "Default")
      (node (ref "U2") (pin "1") (pinfunction "VBAT_1") (pintype "power_in"))
    )
    (net (code "76") (name "unconnected-(U3-DEN(G)-Pad10)") (class "Default")
      (node (ref "U3") (pin "10") (pinfunction "DEN(G)_10") (pintype "bidirectional"))
    )
    (net (code "77") (name "unconnected-(U3-DRDY(G)-Pad12)") (class "Default")
      (node (ref "U3") (pin "12") (pinfunction "DRDY(G)_12") (pintype "bidirectional"))
    )
    (net (code "78") (name "unconnected-(U3-INT(G)-Pad11)") (class "Default")
      (node (ref "U3") (pin "11") (pinfunction "INT(G)_11") (pintype "bidirectional"))
    )
    (net (code "79") (name "unconnected-(U3-INT1(XM)-Pad13)") (class "Default")
      (node (ref "U3") (pin "13") (pinfunction "INT1(XM)_13") (pintype "bidirectional"))
    )
    (net (code "80") (name "unconnected-(U3-INT2(XM)-Pad14)") (class "Default")
      (node (ref "U3") (pin "14") (pinfunction "INT2(XM)_14") (pintype "bidirectional"))
    )
    (net (code "81") (name "unconnected-(U4-A0-Pad7)") (class "Default")
      (node (ref "U4") (pin "7") (pinfunction "A0_7") (pintype "input"))
    )
    (net (code "82") (name "unconnected-(U4-FAULTN-Pad6)") (class "Default")
      (node (ref "U4") (pin "6") (pinfunction "FAULTN_6") (pintype "output"))
    )
    (net (code "83") (name "unconnected-(USER-Pad4)") (class "Default")
      (node (ref "USER") (pin "4") (pinfunction "4_4") (pintype "passive"))
    )
    (net (code "84") (name "unconnected-(WIFI-Pad3)") (class "Default")
      (node (ref "WIFI") (pin "3") (pinfunction "3_3") (pintype "passive"))
    )
    (net (code "85") (name "unconnected-(WIFI-Pad5)") (class "Default")
      (node (ref "WIFI") (pin "5") (pinfunction "5_5") (pintype "passive"))
    )
    (net (code "86") (name "unconnected-(X1-Pad4)") (class "Default")
      (node (ref "X1") (pin "4") (pinfunction "4_4") (pintype "passive"))
    )
  )
)
